# faulhaber.net
KiCad netlist of a schematic drawn in Altium Designer
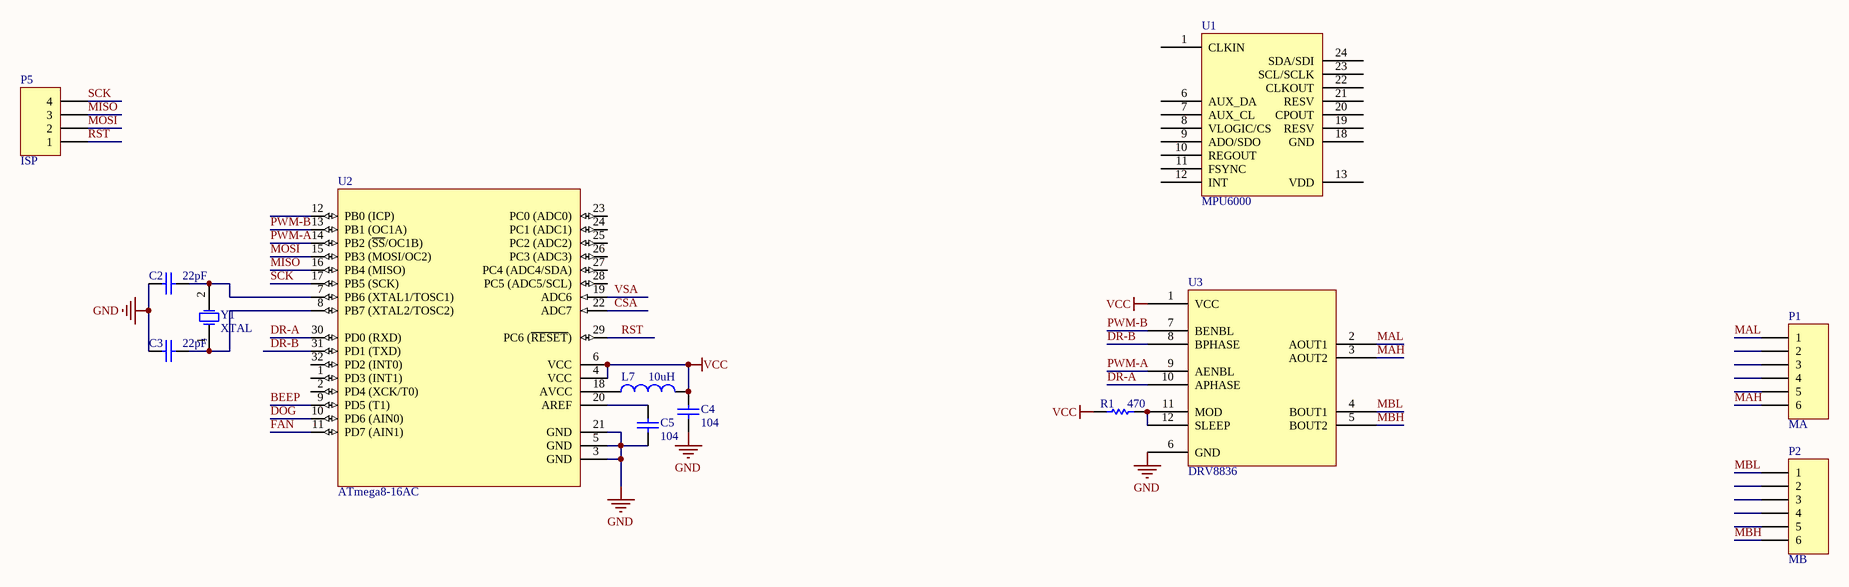
[diagram p0: faulhaber.SchDoc]

(export (version "E")
  (design (tool "Eeschema 10.0.6"))
  (components
    (comp (ref "C2")
      (value "22pF")
      (footprint "0603")
      (description "Capacitor")
      (fields (field (name "Comment") "Cap") (field (name "PUBLISHER") "Altium Limited"))
      (libsource (lib "Miscellaneous Devices") (part "Cap"))
    )
    (comp (ref "C3")
      (value "22pF")
      (footprint "0603")
      (description "Capacitor")
      (fields (field (name "Comment") "Cap") (field (name "PUBLISHER") "Altium Limited"))
      (libsource (lib "Miscellaneous Devices") (part "Cap"))
    )
    (comp (ref "C4")
      (value "104")
      (footprint "0603")
      (description "Capacitor")
      (fields (field (name "Comment") "Cap") (field (name "PUBLISHER") "Altium Limited"))
      (libsource (lib "Miscellaneous Devices") (part "Cap"))
    )
    (comp (ref "C5")
      (value "104")
      (footprint "0603")
      (description "Capacitor")
      (fields (field (name "Comment") "Cap") (field (name "PUBLISHER") "Altium Limited"))
      (libsource (lib "Miscellaneous Devices") (part "Cap"))
    )
    (comp (ref "L7")
      (value "10uH")
      (footprint "0603")
      (description "Inductor")
      (fields (field (name "PUBLISHER") "Altium Limited"))
      (libsource (lib "Miscellaneous Devices") (part "Inductor"))
    )
    (comp (ref "P1")
      (value "MA")
      (footprint "HDR1X6")
      (description "Header, 6-Pin")
      (fields (field (name "PUBLISHER") "Altium Limited"))
      (libsource (lib "Miscellaneous Connectors") (part "Header 6"))
    )
    (comp (ref "P2")
      (value "MB")
      (footprint "HDR1X6")
      (description "Header, 6-Pin")
      (fields (field (name "PUBLISHER") "Altium Limited"))
      (libsource (lib "Miscellaneous Connectors") (part "Header 6"))
    )
    (comp (ref "P5")
      (value "ISP")
      (footprint "HDR1X4")
      (description "Header, 4-Pin")
      (fields (field (name "PUBLISHER") "Altium Limited"))
      (libsource (lib "Miscellaneous Connectors") (part "Header 4"))
    )
    (comp (ref "R1")
      (value "470")
      (footprint "0603")
      (description "Resistor")
      (fields (field (name "Comment") "Res1") (field (name "PUBLISHER") "Altium Limited"))
      (libsource (lib "Miscellaneous Devices") (part "Res1"))
    )
    (comp (ref "U1") (value "MPU6000") (footprint "MPU-6000") (libsource (lib "TANK") (part "MPU-6000")))
    (comp (ref "U2")
      (value "ATmega8-16AC")
      (footprint "32A_M")
      (description "8-Bit AVR Microcontroller with 8K Bytes of In-System Programmable Flash Memory")
      (fields (field (name "PUBLISHER") "Altium Limited"))
      (libsource (lib "Atmel Microcontroller 8-Bit AVR") (part "ATmega8-16AC"))
    )
    (comp (ref "U3") (value "DRV8836") (footprint "WSON-8") (libsource (lib "TANK") (part "DRV8836")))
    (comp (ref "Y1")
      (value "XTAL")
      (footprint "49SD")
      (description "Crystal Oscillator")
      (fields (field (name "PUBLISHER") "Altium Limited"))
      (libsource (lib "Miscellaneous Devices") (part "XTAL"))
    )
  )
  (nets
    (net (code "1") (name "/BEEP") (class "Default")
      (node (ref "U2") (pin "9") (pinfunction "PD5_(T1)_9") (pintype "bidirectional"))
    )
    (net (code "2") (name "/CSA") (class "Default")
      (node (ref "U2") (pin "22") (pinfunction "ADC7_22") (pintype "input"))
    )
    (net (code "3") (name "/DOG") (class "Default")
      (node (ref "U2") (pin "10") (pinfunction "PD6_(AIN0)_10") (pintype "bidirectional"))
    )
    (net (code "4") (name "/DR-A") (class "Default")
      (node (ref "U2") (pin "30") (pinfunction "PD0_(RXD)_30") (pintype "bidirectional"))
      (node (ref "U3") (pin "10") (pinfunction "APHASE_10") (pintype "passive"))
    )
    (net (code "5") (name "/DR-B") (class "Default")
      (node (ref "U2") (pin "31") (pinfunction "PD1_(TXD)_31") (pintype "bidirectional"))
      (node (ref "U3") (pin "8") (pinfunction "BPHASE_8") (pintype "passive"))
    )
    (net (code "6") (name "/FAN") (class "Default")
      (node (ref "U2") (pin "11") (pinfunction "PD7_(AIN1)_11") (pintype "bidirectional"))
    )
    (net (code "7") (name "/MAH") (class "Default")
      (node (ref "P1") (pin "6") (pinfunction "6_6") (pintype "passive"))
      (node (ref "U3") (pin "3") (pinfunction "AOUT2_3") (pintype "passive"))
    )
    (net (code "8") (name "/MAL") (class "Default")
      (node (ref "P1") (pin "1") (pinfunction "1_1") (pintype "passive"))
      (node (ref "U3") (pin "2") (pinfunction "AOUT1_2") (pintype "passive"))
    )
    (net (code "9") (name "/MBH") (class "Default")
      (node (ref "P2") (pin "6") (pinfunction "6_6") (pintype "passive"))
      (node (ref "U3") (pin "5") (pinfunction "BOUT2_5") (pintype "passive"))
    )
    (net (code "10") (name "/MBL") (class "Default")
      (node (ref "P2") (pin "1") (pinfunction "1_1") (pintype "passive"))
      (node (ref "U3") (pin "4") (pinfunction "BOUT1_4") (pintype "passive"))
    )
    (net (code "11") (name "/MISO") (class "Default")
      (node (ref "P5") (pin "3") (pinfunction "3_3") (pintype "passive"))
      (node (ref "U2") (pin "16") (pinfunction "PB4_(MISO)_16") (pintype "bidirectional"))
    )
    (net (code "12") (name "/MOSI") (class "Default")
      (node (ref "P5") (pin "2") (pinfunction "2_2") (pintype "passive"))
      (node (ref "U2") (pin "15") (pinfunction "PB3_(MOSI/OC2)_15") (pintype "bidirectional"))
    )
    (net (code "13") (name "/PWM-A") (class "Default")
      (node (ref "U2") (pin "14") (pinfunction "PB2_(~{SS}/OC1B)_14") (pintype "bidirectional"))
      (node (ref "U3") (pin "9") (pinfunction "AENBL_9") (pintype "passive"))
    )
    (net (code "14") (name "/PWM-B") (class "Default")
      (node (ref "U2") (pin "13") (pinfunction "PB1_(OC1A)_13") (pintype "bidirectional"))
      (node (ref "U3") (pin "7") (pinfunction "BENBL_7") (pintype "passive"))
    )
    (net (code "15") (name "/RST") (class "Default")
      (node (ref "P5") (pin "1") (pinfunction "1_1") (pintype "passive"))
      (node (ref "U2") (pin "29") (pinfunction "PC6_(~{RESET})_29") (pintype "bidirectional"))
    )
    (net (code "16") (name "/SCK") (class "Default")
      (node (ref "P5") (pin "4") (pinfunction "4_4") (pintype "passive"))
      (node (ref "U2") (pin "17") (pinfunction "PB5_(SCK)_17") (pintype "bidirectional"))
    )
    (net (code "17") (name "/VSA") (class "Default")
      (node (ref "U2") (pin "19") (pinfunction "ADC6_19") (pintype "input"))
    )
    (net (code "18") (name "GND") (class "Default")
      (node (ref "C2") (pin "2") (pinfunction "2_2") (pintype "passive"))
      (node (ref "C3") (pin "2") (pinfunction "2_2") (pintype "passive"))
      (node (ref "C4") (pin "2") (pinfunction "2_2") (pintype "passive"))
      (node (ref "C5") (pin "2") (pinfunction "2_2") (pintype "passive"))
      (node (ref "U2") (pin "21") (pinfunction "GND_21") (pintype "power_in"))
      (node (ref "U2") (pin "3") (pinfunction "GND_3") (pintype "power_in"))
      (node (ref "U2") (pin "5") (pinfunction "GND_5") (pintype "power_in"))
      (node (ref "U3") (pin "6") (pinfunction "GND_6") (pintype "passive"))
    )
    (net (code "19") (name "Net-(U2-AREF)") (class "Default")
      (node (ref "C5") (pin "1") (pinfunction "1_1") (pintype "passive"))
      (node (ref "U2") (pin "20") (pinfunction "AREF_20") (pintype "passive"))
    )
    (net (code "20") (name "Net-(U2-AVCC)") (class "Default")
      (node (ref "L7") (pin "1") (pinfunction "1_1") (pintype "passive"))
      (node (ref "U2") (pin "18") (pinfunction "AVCC_18") (pintype "power_in"))
    )
    (net (code "21") (name "Net-(U2-PB6_(XTAL1{slash}TOSC1))") (class "Default")
      (node (ref "C2") (pin "1") (pinfunction "1_1") (pintype "passive"))
      (node (ref "U2") (pin "7") (pinfunction "PB6_(XTAL1/TOSC1)_7") (pintype "bidirectional"))
      (node (ref "Y1") (pin "2") (pinfunction "OSC2_2") (pintype "passive"))
    )
    (net (code "22") (name "Net-(U2-PB7_(XTAL2{slash}TOSC2))") (class "Default")
      (node (ref "C3") (pin "1") (pinfunction "1_1") (pintype "passive"))
      (node (ref "U2") (pin "8") (pinfunction "PB7_(XTAL2/TOSC2)_8") (pintype "bidirectional"))
      (node (ref "Y1") (pin "1") (pinfunction "OSC1_1") (pintype "passive"))
    )
    (net (code "23") (name "Net-(U3-MOD)") (class "Default")
      (node (ref "R1") (pin "2") (pinfunction "2_2") (pintype "passive"))
      (node (ref "U3") (pin "11") (pinfunction "MOD_11") (pintype "passive"))
      (node (ref "U3") (pin "12") (pinfunction "SLEEP_12") (pintype "passive"))
    )
    (net (code "24") (name "VCC") (class "Default")
      (node (ref "C4") (pin "1") (pinfunction "1_1") (pintype "passive"))
      (node (ref "L7") (pin "2") (pinfunction "2_2") (pintype "passive"))
      (node (ref "R1") (pin "1") (pinfunction "1_1") (pintype "passive"))
      (node (ref "U2") (pin "4") (pinfunction "VCC_4") (pintype "power_in"))
      (node (ref "U2") (pin "6") (pinfunction "VCC_6") (pintype "power_in"))
      (node (ref "U3") (pin "1") (pinfunction "VCC_1") (pintype "passive"))
    )
    (net (code "25") (name "unconnected-(P1-Pad2)") (class "Default")
      (node (ref "P1") (pin "2") (pinfunction "2_2") (pintype "passive"))
    )
    (net (code "26") (name "unconnected-(P1-Pad3)") (class "Default")
      (node (ref "P1") (pin "3") (pinfunction "3_3") (pintype "passive"))
    )
    (net (code "27") (name "unconnected-(P1-Pad4)") (class "Default")
      (node (ref "P1") (pin "4") (pinfunction "4_4") (pintype "passive"))
    )
    (net (code "28") (name "unconnected-(P1-Pad5)") (class "Default")
      (node (ref "P1") (pin "5") (pinfunction "5_5") (pintype "passive"))
    )
    (net (code "29") (name "unconnected-(P2-Pad2)") (class "Default")
      (node (ref "P2") (pin "2") (pinfunction "2_2") (pintype "passive"))
    )
    (net (code "30") (name "unconnected-(P2-Pad3)") (class "Default")
      (node (ref "P2") (pin "3") (pinfunction "3_3") (pintype "passive"))
    )
    (net (code "31") (name "unconnected-(P2-Pad4)") (class "Default")
      (node (ref "P2") (pin "4") (pinfunction "4_4") (pintype "passive"))
    )
    (net (code "32") (name "unconnected-(P2-Pad5)") (class "Default")
      (node (ref "P2") (pin "5") (pinfunction "5_5") (pintype "passive"))
    )
    (net (code "33") (name "unconnected-(U1-ADO{slash}SDO-Pad9)") (class "Default")
      (node (ref "U1") (pin "9") (pinfunction "ADO/SDO_9") (pintype "passive"))
    )
    (net (code "34") (name "unconnected-(U1-AUX_CL-Pad7)") (class "Default")
      (node (ref "U1") (pin "7") (pinfunction "AUX_CL_7") (pintype "passive"))
    )
    (net (code "35") (name "unconnected-(U1-AUX_DA-Pad6)") (class "Default")
      (node (ref "U1") (pin "6") (pinfunction "AUX_DA_6") (pintype "passive"))
    )
    (net (code "36") (name "unconnected-(U1-CLKIN-Pad1)") (class "Default")
      (node (ref "U1") (pin "1") (pinfunction "CLKIN_1") (pintype "passive"))
    )
    (net (code "37") (name "unconnected-(U1-CLKOUT-Pad22)") (class "Default")
      (node (ref "U1") (pin "22") (pinfunction "CLKOUT_22") (pintype "passive"))
    )
    (net (code "38") (name "unconnected-(U1-CPOUT-Pad20)") (class "Default")
      (node (ref "U1") (pin "20") (pinfunction "CPOUT_20") (pintype "passive"))
    )
    (net (code "39") (name "unconnected-(U1-FSYNC-Pad11)") (class "Default")
      (node (ref "U1") (pin "11") (pinfunction "FSYNC_11") (pintype "passive"))
    )
    (net (code "40") (name "unconnected-(U1-GND-Pad18)") (class "Default")
      (node (ref "U1") (pin "18") (pinfunction "GND_18") (pintype "passive"))
    )
    (net (code "41") (name "unconnected-(U1-INT-Pad12)") (class "Default")
      (node (ref "U1") (pin "12") (pinfunction "INT_12") (pintype "passive"))
    )
    (net (code "42") (name "unconnected-(U1-REGOUT-Pad10)") (class "Default")
      (node (ref "U1") (pin "10") (pinfunction "REGOUT_10") (pintype "passive"))
    )
    (net (code "43") (name "unconnected-(U1-RESV-Pad19)") (class "Default")
      (node (ref "U1") (pin "19") (pinfunction "RESV_19") (pintype "passive"))
    )
    (net (code "44") (name "unconnected-(U1-RESV-Pad21)") (class "Default")
      (node (ref "U1") (pin "21") (pinfunction "RESV_21") (pintype "passive"))
    )
    (net (code "45") (name "unconnected-(U1-SCL{slash}SCLK-Pad23)") (class "Default")
      (node (ref "U1") (pin "23") (pinfunction "SCL/SCLK_23") (pintype "passive"))
    )
    (net (code "46") (name "unconnected-(U1-SDA{slash}SDI-Pad24)") (class "Default")
      (node (ref "U1") (pin "24") (pinfunction "SDA/SDI_24") (pintype "passive"))
    )
    (net (code "47") (name "unconnected-(U1-VDD-Pad13)") (class "Default")
      (node (ref "U1") (pin "13") (pinfunction "VDD_13") (pintype "passive"))
    )
    (net (code "48") (name "unconnected-(U1-VLOGIC{slash}CS-Pad8)") (class "Default")
      (node (ref "U1") (pin "8") (pinfunction "VLOGIC/CS_8") (pintype "passive"))
    )
    (net (code "49") (name "unconnected-(U2-PB0_(ICP)-Pad12)") (class "Default")
      (node (ref "U2") (pin "12") (pinfunction "PB0_(ICP)_12") (pintype "bidirectional"))
    )
    (net (code "50") (name "unconnected-(U2-PC0_(ADC0)-Pad23)") (class "Default")
      (node (ref "U2") (pin "23") (pinfunction "PC0_(ADC0)_23") (pintype "bidirectional"))
    )
    (net (code "51") (name "unconnected-(U2-PC1_(ADC1)-Pad24)") (class "Default")
      (node (ref "U2") (pin "24") (pinfunction "PC1_(ADC1)_24") (pintype "bidirectional"))
    )
    (net (code "52") (name "unconnected-(U2-PC2_(ADC2)-Pad25)") (class "Default")
      (node (ref "U2") (pin "25") (pinfunction "PC2_(ADC2)_25") (pintype "bidirectional"))
    )
    (net (code "53") (name "unconnected-(U2-PC3_(ADC3)-Pad26)") (class "Default")
      (node (ref "U2") (pin "26") (pinfunction "PC3_(ADC3)_26") (pintype "bidirectional"))
    )
    (net (code "54") (name "unconnected-(U2-PC4_(ADC4{slash}SDA)-Pad27)") (class "Default")
      (node (ref "U2") (pin "27") (pinfunction "PC4_(ADC4/SDA)_27") (pintype "bidirectional"))
    )
    (net (code "55") (name "unconnected-(U2-PC5_(ADC5{slash}SCL)-Pad28)") (class "Default")
      (node (ref "U2") (pin "28") (pinfunction "PC5_(ADC5/SCL)_28") (pintype "bidirectional"))
    )
    (net (code "56") (name "unconnected-(U2-PD2_(INT0)-Pad32)") (class "Default")
      (node (ref "U2") (pin "32") (pinfunction "PD2_(INT0)_32") (pintype "bidirectional"))
    )
    (net (code "57") (name "unconnected-(U2-PD3_(INT1)-Pad1)") (class "Default")
      (node (ref "U2") (pin "1") (pinfunction "PD3_(INT1)_1") (pintype "bidirectional"))
    )
    (net (code "58") (name "unconnected-(U2-PD4_(XCK{slash}T0)-Pad2)") (class "Default")
      (node (ref "U2") (pin "2") (pinfunction "PD4_(XCK/T0)_2") (pintype "bidirectional"))
    )
  )
)
